# uhu-adapter.net
KiCad netlist of a schematic drawn in EAGLE
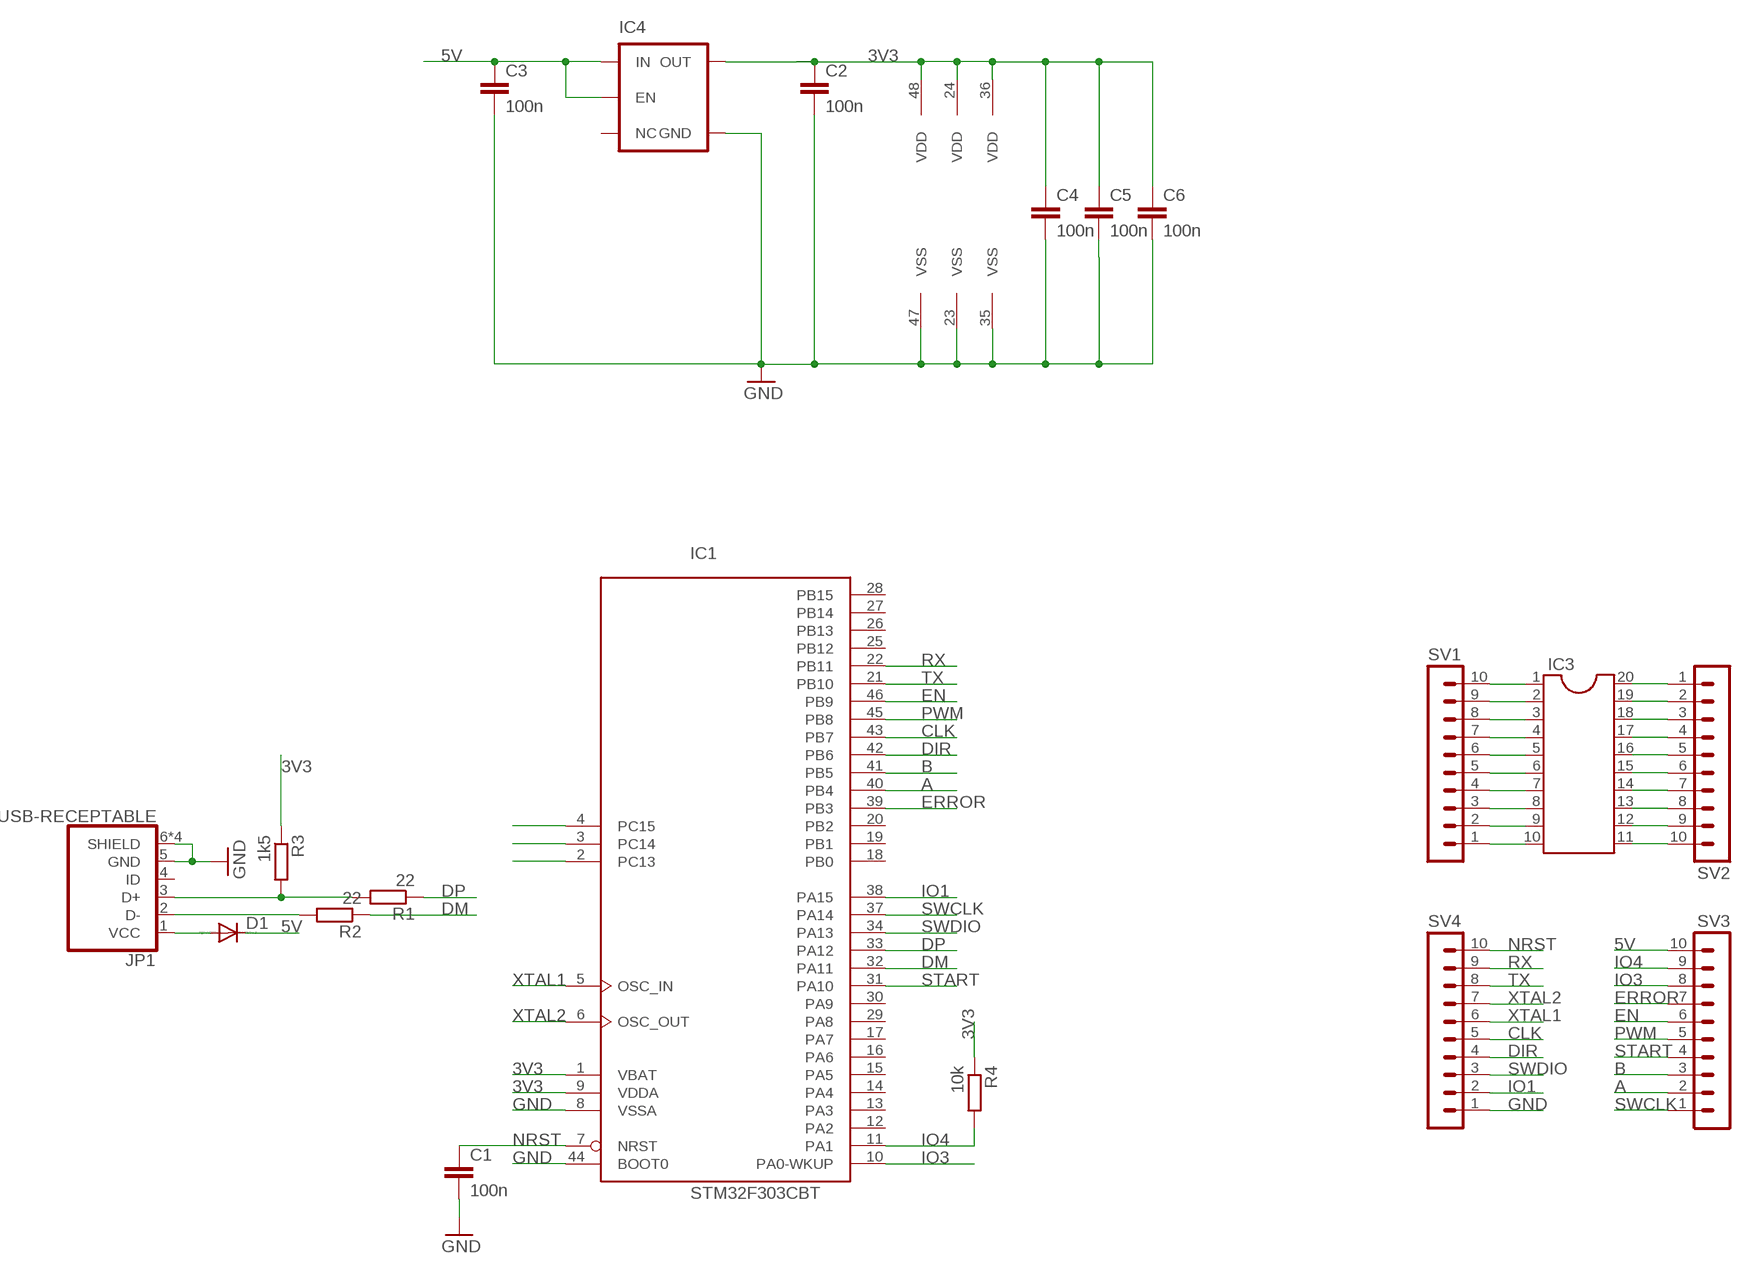
[diagram p0: schematic, sheet 1]

(export (version "E")
  (design (tool "Eeschema 10.0.6"))
  (components
    (comp (ref "C1")
      (value "100n")
      (footprint "eagle-import:C0603")
      (libsource (lib "eagle-import") (part "C-EUC0603"))
    )
    (comp (ref "C2")
      (value "100n")
      (footprint "eagle-import:C0603")
      (libsource (lib "eagle-import") (part "C-EUC0603"))
    )
    (comp (ref "C3")
      (value "100n")
      (footprint "eagle-import:C0603")
      (libsource (lib "eagle-import") (part "C-EUC0603"))
    )
    (comp (ref "C4")
      (value "100n")
      (footprint "eagle-import:C0603")
      (libsource (lib "eagle-import") (part "C-EUC0603"))
    )
    (comp (ref "C5")
      (value "100n")
      (footprint "eagle-import:C0603")
      (libsource (lib "eagle-import") (part "C-EUC0603"))
    )
    (comp (ref "C6")
      (value "100n")
      (footprint "eagle-import:C0603")
      (libsource (lib "eagle-import") (part "C-EUC0603"))
    )
    (comp (ref "D1")
      (value "DIODE-SOD123")
      (footprint "eagle-import:SOD123")
      (libsource (lib "eagle-import") (part "DIODE-SOD123"))
    )
    (comp (ref "IC1")
      (value "STM32F303CBT")
      (footprint "eagle-import:LQFP48")
      (libsource (lib "eagle-import") (part "STM32F303CTB"))
    )
    (comp (ref "IC3")
      (value "DIL20")
      (footprint "eagle-import:DIL20")
      (libsource (lib "eagle-import") (part "DIL20"))
    )
    (comp (ref "IC4")
      (value "V_REG_TPS76433SOT23-5")
      (footprint "eagle-import:SOT23-5")
      (libsource (lib "eagle-import") (part "V_REG_TPS76433SOT23-5"))
    )
    (comp (ref "JP1")
      (value "USB-RECEPTABLE")
      (footprint "eagle-import:FCI-10103594-0001LF")
      (libsource (lib "eagle-import") (part "USB-RECEPTABLE"))
    )
    (comp (ref "R1")
      (value "22")
      (footprint "eagle-import:R0603")
      (libsource (lib "eagle-import") (part "R-EU_R0603"))
    )
    (comp (ref "R2")
      (value "22")
      (footprint "eagle-import:R0603")
      (libsource (lib "eagle-import") (part "R-EU_R0603"))
    )
    (comp (ref "R3")
      (value "1k5")
      (footprint "eagle-import:R0603")
      (libsource (lib "eagle-import") (part "R-EU_R0603"))
    )
    (comp (ref "R4")
      (value "10k")
      (footprint "eagle-import:R0603")
      (libsource (lib "eagle-import") (part "R-EU_R0603"))
    )
    (comp (ref "SV1")
      (value "MA10-1")
      (footprint "eagle-import:MA10-1")
      (libsource (lib "eagle-import") (part "MA10-1"))
    )
    (comp (ref "SV2")
      (value "MA10-1")
      (footprint "eagle-import:MA10-1")
      (libsource (lib "eagle-import") (part "MA10-1"))
    )
    (comp (ref "SV3")
      (value "MA10-1")
      (footprint "eagle-import:MA10-1")
      (libsource (lib "eagle-import") (part "MA10-1"))
    )
    (comp (ref "SV4")
      (value "MA10-1")
      (footprint "eagle-import:MA10-1")
      (libsource (lib "eagle-import") (part "MA10-1"))
    )
  )
  (nets
    (net (code "1") (name "/3V3") (class "Default")
      (node (ref "C2") (pin "1") (pinfunction "1_1") (pintype "passive"))
      (node (ref "C4") (pin "1") (pinfunction "1_1") (pintype "passive"))
      (node (ref "C5") (pin "1") (pinfunction "1_1") (pintype "passive"))
      (node (ref "C6") (pin "1") (pinfunction "1_1") (pintype "passive"))
      (node (ref "IC1") (pin "1") (pinfunction "VBAT_1") (pintype "power_in"))
      (node (ref "IC1") (pin "24") (pinfunction "VDD_24") (pintype "power_in"))
      (node (ref "IC1") (pin "36") (pinfunction "VDD_36") (pintype "power_in"))
      (node (ref "IC1") (pin "48") (pinfunction "VDD_48") (pintype "power_in"))
      (node (ref "IC1") (pin "9") (pinfunction "VDDA_9") (pintype "power_in"))
      (node (ref "IC4") (pin "5") (pinfunction "OUT_5") (pintype "passive"))
      (node (ref "R3") (pin "1") (pinfunction "1_1") (pintype "passive"))
      (node (ref "R4") (pin "1") (pinfunction "1_1") (pintype "passive"))
    )
    (net (code "2") (name "/5V") (class "Default")
      (node (ref "C3") (pin "1") (pinfunction "1_1") (pintype "passive"))
      (node (ref "D1") (pin "C") (pinfunction "C_C") (pintype "passive"))
      (node (ref "IC4") (pin "1") (pinfunction "IN_1") (pintype "input"))
      (node (ref "IC4") (pin "3") (pinfunction "EN_3") (pintype "input"))
      (node (ref "SV3") (pin "10") (pinfunction "10_10") (pintype "passive"))
    )
    (net (code "3") (name "/A") (class "Default")
      (node (ref "IC1") (pin "40") (pinfunction "PB4_40") (pintype "bidirectional"))
      (node (ref "SV3") (pin "2") (pinfunction "2_2") (pintype "passive"))
    )
    (net (code "4") (name "/B") (class "Default")
      (node (ref "IC1") (pin "41") (pinfunction "PB5_41") (pintype "bidirectional"))
      (node (ref "SV3") (pin "3") (pinfunction "3_3") (pintype "passive"))
    )
    (net (code "5") (name "/CLK") (class "Default")
      (node (ref "IC1") (pin "43") (pinfunction "PB7_43") (pintype "bidirectional"))
      (node (ref "SV4") (pin "5") (pinfunction "5_5") (pintype "passive"))
    )
    (net (code "6") (name "/DIR") (class "Default")
      (node (ref "IC1") (pin "42") (pinfunction "PB6_42") (pintype "bidirectional"))
      (node (ref "SV4") (pin "4") (pinfunction "4_4") (pintype "passive"))
    )
    (net (code "7") (name "/DM") (class "Default")
      (node (ref "IC1") (pin "32") (pinfunction "PA11_32") (pintype "bidirectional"))
      (node (ref "R2") (pin "1") (pinfunction "1_1") (pintype "passive"))
    )
    (net (code "8") (name "/DP") (class "Default")
      (node (ref "IC1") (pin "33") (pinfunction "PA12_33") (pintype "bidirectional"))
      (node (ref "R1") (pin "1") (pinfunction "1_1") (pintype "passive"))
    )
    (net (code "9") (name "/EN") (class "Default")
      (node (ref "IC1") (pin "46") (pinfunction "PB9_46") (pintype "bidirectional"))
      (node (ref "SV3") (pin "6") (pinfunction "6_6") (pintype "passive"))
    )
    (net (code "10") (name "/ERROR") (class "Default")
      (node (ref "IC1") (pin "39") (pinfunction "PB3_39") (pintype "bidirectional"))
      (node (ref "SV3") (pin "7") (pinfunction "7_7") (pintype "passive"))
    )
    (net (code "11") (name "/IO1") (class "Default")
      (node (ref "IC1") (pin "38") (pinfunction "PA15_38") (pintype "bidirectional"))
      (node (ref "SV4") (pin "2") (pinfunction "2_2") (pintype "passive"))
    )
    (net (code "12") (name "/IO3") (class "Default")
      (node (ref "IC1") (pin "10") (pinfunction "PA0-WKUP_10") (pintype "bidirectional"))
      (node (ref "SV3") (pin "8") (pinfunction "8_8") (pintype "passive"))
    )
    (net (code "13") (name "/IO4") (class "Default")
      (node (ref "IC1") (pin "11") (pinfunction "PA1_11") (pintype "bidirectional"))
      (node (ref "R4") (pin "2") (pinfunction "2_2") (pintype "passive"))
      (node (ref "SV3") (pin "9") (pinfunction "9_9") (pintype "passive"))
    )
    (net (code "14") (name "/NRST") (class "Default")
      (node (ref "C1") (pin "1") (pinfunction "1_1") (pintype "passive"))
      (node (ref "IC1") (pin "7") (pinfunction "NRST_7") (pintype "bidirectional"))
      (node (ref "SV4") (pin "10") (pinfunction "10_10") (pintype "passive"))
    )
    (net (code "15") (name "/PWM") (class "Default")
      (node (ref "IC1") (pin "45") (pinfunction "PB8_45") (pintype "bidirectional"))
      (node (ref "SV3") (pin "5") (pinfunction "5_5") (pintype "passive"))
    )
    (net (code "16") (name "/RX") (class "Default")
      (node (ref "IC1") (pin "22") (pinfunction "PB11_22") (pintype "bidirectional"))
      (node (ref "SV4") (pin "9") (pinfunction "9_9") (pintype "passive"))
    )
    (net (code "17") (name "/START") (class "Default")
      (node (ref "IC1") (pin "31") (pinfunction "PA10_31") (pintype "bidirectional"))
      (node (ref "SV3") (pin "4") (pinfunction "4_4") (pintype "passive"))
    )
    (net (code "18") (name "/SWCLK") (class "Default")
      (node (ref "IC1") (pin "37") (pinfunction "PA14_37") (pintype "bidirectional"))
      (node (ref "SV3") (pin "1") (pinfunction "1_1") (pintype "passive"))
    )
    (net (code "19") (name "/SWDIO") (class "Default")
      (node (ref "IC1") (pin "34") (pinfunction "PA13_34") (pintype "bidirectional"))
      (node (ref "SV4") (pin "3") (pinfunction "3_3") (pintype "passive"))
    )
    (net (code "20") (name "/TX") (class "Default")
      (node (ref "IC1") (pin "21") (pinfunction "PB10_21") (pintype "bidirectional"))
      (node (ref "SV4") (pin "8") (pinfunction "8_8") (pintype "passive"))
    )
    (net (code "21") (name "/XTAL1") (class "Default")
      (node (ref "IC1") (pin "5") (pinfunction "OSC_IN_5") (pintype "bidirectional"))
      (node (ref "SV4") (pin "6") (pinfunction "6_6") (pintype "passive"))
    )
    (net (code "22") (name "/XTAL2") (class "Default")
      (node (ref "IC1") (pin "6") (pinfunction "OSC_OUT_6") (pintype "bidirectional"))
      (node (ref "SV4") (pin "7") (pinfunction "7_7") (pintype "passive"))
    )
    (net (code "23") (name "GND") (class "Default")
      (node (ref "C1") (pin "2") (pinfunction "2_2") (pintype "passive"))
      (node (ref "C2") (pin "2") (pinfunction "2_2") (pintype "passive"))
      (node (ref "C3") (pin "2") (pinfunction "2_2") (pintype "passive"))
      (node (ref "C4") (pin "2") (pinfunction "2_2") (pintype "passive"))
      (node (ref "C5") (pin "2") (pinfunction "2_2") (pintype "passive"))
      (node (ref "C6") (pin "2") (pinfunction "2_2") (pintype "passive"))
      (node (ref "IC1") (pin "23") (pinfunction "VSS_23") (pintype "power_in"))
      (node (ref "IC1") (pin "35") (pinfunction "VSS_35") (pintype "power_in"))
      (node (ref "IC1") (pin "44") (pinfunction "BOOT0_44") (pintype "input"))
      (node (ref "IC1") (pin "47") (pinfunction "VSS_47") (pintype "power_in"))
      (node (ref "IC1") (pin "8") (pinfunction "VSSA_8") (pintype "power_in"))
      (node (ref "IC4") (pin "2") (pinfunction "GND_2") (pintype "input"))
      (node (ref "JP1") (pin "5") (pinfunction "GND_5") (pintype "bidirectional"))
      (node (ref "JP1") (pin "6") (pinfunction "SHIELD_6") (pintype "bidirectional"))
      (node (ref "JP1") (pin "7") (pinfunction "SHIELD_7") (pintype "bidirectional"))
      (node (ref "JP1") (pin "8") (pinfunction "SHIELD_8") (pintype "bidirectional"))
      (node (ref "JP1") (pin "9") (pinfunction "SHIELD_9") (pintype "bidirectional"))
      (node (ref "SV4") (pin "1") (pinfunction "1_1") (pintype "passive"))
    )
    (net (code "24") (name "Net-(IC3-Pad1)") (class "Default")
      (node (ref "IC3") (pin "1") (pinfunction "1_1") (pintype "passive"))
      (node (ref "SV1") (pin "10") (pinfunction "10_10") (pintype "passive"))
    )
    (net (code "25") (name "Net-(IC3-Pad2)") (class "Default")
      (node (ref "IC3") (pin "2") (pinfunction "2_2") (pintype "passive"))
      (node (ref "SV1") (pin "9") (pinfunction "9_9") (pintype "passive"))
    )
    (net (code "26") (name "Net-(IC3-Pad3)") (class "Default")
      (node (ref "IC3") (pin "3") (pinfunction "3_3") (pintype "passive"))
      (node (ref "SV1") (pin "8") (pinfunction "8_8") (pintype "passive"))
    )
    (net (code "27") (name "Net-(IC3-Pad4)") (class "Default")
      (node (ref "IC3") (pin "4") (pinfunction "4_4") (pintype "passive"))
      (node (ref "SV1") (pin "7") (pinfunction "7_7") (pintype "passive"))
    )
    (net (code "28") (name "Net-(IC3-Pad5)") (class "Default")
      (node (ref "IC3") (pin "5") (pinfunction "5_5") (pintype "passive"))
      (node (ref "SV1") (pin "6") (pinfunction "6_6") (pintype "passive"))
    )
    (net (code "29") (name "Net-(IC3-Pad6)") (class "Default")
      (node (ref "IC3") (pin "6") (pinfunction "6_6") (pintype "passive"))
      (node (ref "SV1") (pin "5") (pinfunction "5_5") (pintype "passive"))
    )
    (net (code "30") (name "Net-(IC3-Pad7)") (class "Default")
      (node (ref "IC3") (pin "7") (pinfunction "7_7") (pintype "passive"))
      (node (ref "SV1") (pin "4") (pinfunction "4_4") (pintype "passive"))
    )
    (net (code "31") (name "Net-(IC3-Pad8)") (class "Default")
      (node (ref "IC3") (pin "8") (pinfunction "8_8") (pintype "passive"))
      (node (ref "SV1") (pin "3") (pinfunction "3_3") (pintype "passive"))
    )
    (net (code "32") (name "Net-(IC3-Pad9)") (class "Default")
      (node (ref "IC3") (pin "9") (pinfunction "9_9") (pintype "passive"))
      (node (ref "SV1") (pin "2") (pinfunction "2_2") (pintype "passive"))
    )
    (net (code "33") (name "Net-(IC3-Pad10)") (class "Default")
      (node (ref "IC3") (pin "10") (pinfunction "10_10") (pintype "passive"))
      (node (ref "SV1") (pin "1") (pinfunction "1_1") (pintype "passive"))
    )
    (net (code "34") (name "Net-(IC3-Pad11)") (class "Default")
      (node (ref "IC3") (pin "11") (pinfunction "11_11") (pintype "passive"))
      (node (ref "SV2") (pin "10") (pinfunction "10_10") (pintype "passive"))
    )
    (net (code "35") (name "Net-(IC3-Pad12)") (class "Default")
      (node (ref "IC3") (pin "12") (pinfunction "12_12") (pintype "passive"))
      (node (ref "SV2") (pin "9") (pinfunction "9_9") (pintype "passive"))
    )
    (net (code "36") (name "Net-(IC3-Pad13)") (class "Default")
      (node (ref "IC3") (pin "13") (pinfunction "13_13") (pintype "passive"))
      (node (ref "SV2") (pin "8") (pinfunction "8_8") (pintype "passive"))
    )
    (net (code "37") (name "Net-(IC3-Pad14)") (class "Default")
      (node (ref "IC3") (pin "14") (pinfunction "14_14") (pintype "passive"))
      (node (ref "SV2") (pin "7") (pinfunction "7_7") (pintype "passive"))
    )
    (net (code "38") (name "Net-(IC3-Pad15)") (class "Default")
      (node (ref "IC3") (pin "15") (pinfunction "15_15") (pintype "passive"))
      (node (ref "SV2") (pin "6") (pinfunction "6_6") (pintype "passive"))
    )
    (net (code "39") (name "Net-(IC3-Pad16)") (class "Default")
      (node (ref "IC3") (pin "16") (pinfunction "16_16") (pintype "passive"))
      (node (ref "SV2") (pin "5") (pinfunction "5_5") (pintype "passive"))
    )
    (net (code "40") (name "Net-(IC3-Pad17)") (class "Default")
      (node (ref "IC3") (pin "17") (pinfunction "17_17") (pintype "passive"))
      (node (ref "SV2") (pin "4") (pinfunction "4_4") (pintype "passive"))
    )
    (net (code "41") (name "Net-(IC3-Pad18)") (class "Default")
      (node (ref "IC3") (pin "18") (pinfunction "18_18") (pintype "passive"))
      (node (ref "SV2") (pin "3") (pinfunction "3_3") (pintype "passive"))
    )
    (net (code "42") (name "Net-(IC3-Pad19)") (class "Default")
      (node (ref "IC3") (pin "19") (pinfunction "19_19") (pintype "passive"))
      (node (ref "SV2") (pin "2") (pinfunction "2_2") (pintype "passive"))
    )
    (net (code "43") (name "Net-(IC3-Pad20)") (class "Default")
      (node (ref "IC3") (pin "20") (pinfunction "20_20") (pintype "passive"))
      (node (ref "SV2") (pin "1") (pinfunction "1_1") (pintype "passive"))
    )
    (net (code "44") (name "Net-(JP1-D+)") (class "Default")
      (node (ref "JP1") (pin "3") (pinfunction "D+_3") (pintype "bidirectional"))
      (node (ref "R1") (pin "2") (pinfunction "2_2") (pintype "passive"))
      (node (ref "R3") (pin "2") (pinfunction "2_2") (pintype "passive"))
    )
    (net (code "45") (name "Net-(JP1-D-)") (class "Default")
      (node (ref "JP1") (pin "2") (pinfunction "D-_2") (pintype "bidirectional"))
      (node (ref "R2") (pin "2") (pinfunction "2_2") (pintype "passive"))
    )
    (net (code "46") (name "Net-(JP1-VCC)") (class "Default")
      (node (ref "D1") (pin "A") (pinfunction "A_A") (pintype "passive"))
      (node (ref "JP1") (pin "1") (pinfunction "VCC_1") (pintype "bidirectional"))
    )
    (net (code "47") (name "unconnected-(IC1A-PA2-Pad12)") (class "Default")
      (node (ref "IC1") (pin "12") (pinfunction "PA2_12") (pintype "bidirectional"))
    )
    (net (code "48") (name "unconnected-(IC1A-PA3-Pad13)") (class "Default")
      (node (ref "IC1") (pin "13") (pinfunction "PA3_13") (pintype "bidirectional"))
    )
    (net (code "49") (name "unconnected-(IC1A-PA4-Pad14)") (class "Default")
      (node (ref "IC1") (pin "14") (pinfunction "PA4_14") (pintype "bidirectional"))
    )
    (net (code "50") (name "unconnected-(IC1A-PA5-Pad15)") (class "Default")
      (node (ref "IC1") (pin "15") (pinfunction "PA5_15") (pintype "bidirectional"))
    )
    (net (code "51") (name "unconnected-(IC1A-PA6-Pad16)") (class "Default")
      (node (ref "IC1") (pin "16") (pinfunction "PA6_16") (pintype "bidirectional"))
    )
    (net (code "52") (name "unconnected-(IC1A-PA7-Pad17)") (class "Default")
      (node (ref "IC1") (pin "17") (pinfunction "PA7_17") (pintype "bidirectional"))
    )
    (net (code "53") (name "unconnected-(IC1A-PA8-Pad29)") (class "Default")
      (node (ref "IC1") (pin "29") (pinfunction "PA8_29") (pintype "bidirectional"))
    )
    (net (code "54") (name "unconnected-(IC1A-PA9-Pad30)") (class "Default")
      (node (ref "IC1") (pin "30") (pinfunction "PA9_30") (pintype "bidirectional"))
    )
    (net (code "55") (name "unconnected-(IC1A-PB0-Pad18)") (class "Default")
      (node (ref "IC1") (pin "18") (pinfunction "PB0_18") (pintype "bidirectional"))
    )
    (net (code "56") (name "unconnected-(IC1A-PB1-Pad19)") (class "Default")
      (node (ref "IC1") (pin "19") (pinfunction "PB1_19") (pintype "bidirectional"))
    )
    (net (code "57") (name "unconnected-(IC1A-PB2-Pad20)") (class "Default")
      (node (ref "IC1") (pin "20") (pinfunction "PB2_20") (pintype "bidirectional"))
    )
    (net (code "58") (name "unconnected-(IC1A-PB12-Pad25)") (class "Default")
      (node (ref "IC1") (pin "25") (pinfunction "PB12_25") (pintype "bidirectional"))
    )
    (net (code "59") (name "unconnected-(IC1A-PB13-Pad26)") (class "Default")
      (node (ref "IC1") (pin "26") (pinfunction "PB13_26") (pintype "bidirectional"))
    )
    (net (code "60") (name "unconnected-(IC1A-PB14-Pad27)") (class "Default")
      (node (ref "IC1") (pin "27") (pinfunction "PB14_27") (pintype "bidirectional"))
    )
    (net (code "61") (name "unconnected-(IC1A-PB15-Pad28)") (class "Default")
      (node (ref "IC1") (pin "28") (pinfunction "PB15_28") (pintype "bidirectional"))
    )
    (net (code "62") (name "unconnected-(IC1A-PC13-Pad2)") (class "Default")
      (node (ref "IC1") (pin "2") (pinfunction "PC13_2") (pintype "bidirectional"))
    )
    (net (code "63") (name "unconnected-(IC1A-PC14-Pad3)") (class "Default")
      (node (ref "IC1") (pin "3") (pinfunction "PC14_3") (pintype "bidirectional"))
    )
    (net (code "64") (name "unconnected-(IC1A-PC15-Pad4)") (class "Default")
      (node (ref "IC1") (pin "4") (pinfunction "PC15_4") (pintype "bidirectional"))
    )
    (net (code "65") (name "unconnected-(IC4-NC-Pad4)") (class "Default")
      (node (ref "IC4") (pin "4") (pinfunction "NC_4") (pintype "input"))
    )
    (net (code "66") (name "unconnected-(JP1-ID-Pad4)") (class "Default")
      (node (ref "JP1") (pin "4") (pinfunction "ID_4") (pintype "bidirectional"))
    )
  )
)
